# Main_Sheet.net
KiCad netlist of a schematic drawn in Altium Designer
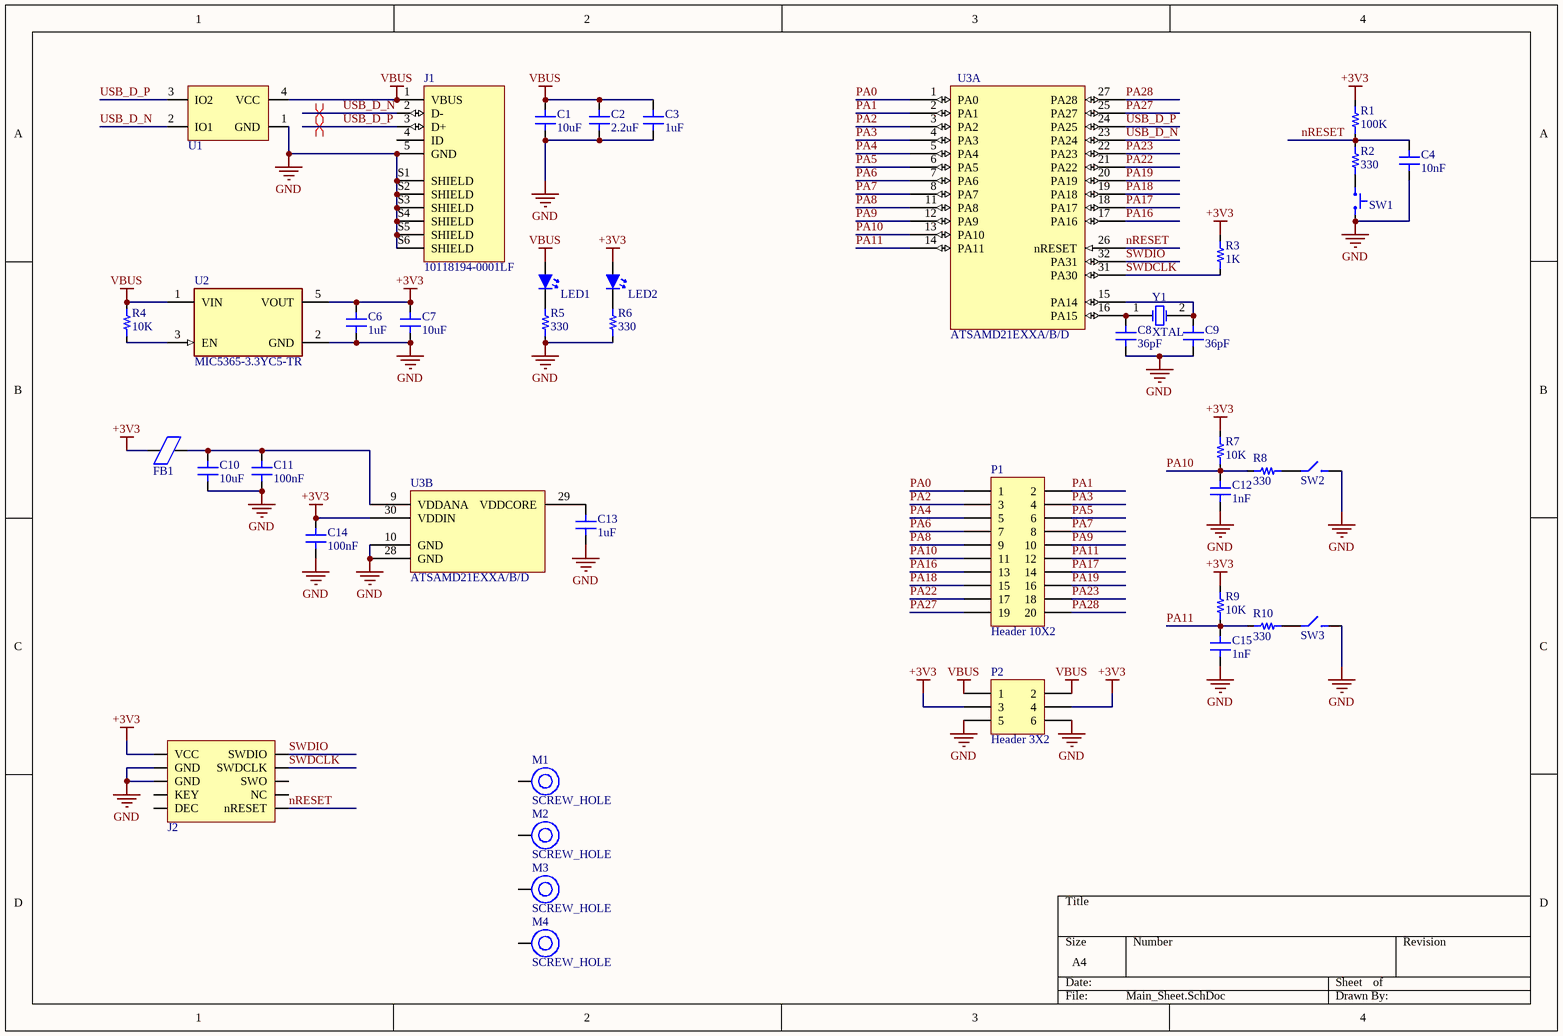
[diagram p0: Main_Sheet.SchDoc]

(export (version "E")
  (design (tool "Eeschema 10.0.6"))
  (components
    (comp (ref "C1")
      (value "10uF")
      (footprint "C0603")
      (fields (field (name "Comment") "Cap"))
      (libsource (lib "Brandon-Lib") (part "Cap"))
    )
    (comp (ref "C2")
      (value "2.2uF")
      (footprint "C0603")
      (fields (field (name "Comment") "Cap"))
      (libsource (lib "Brandon-Lib") (part "Cap"))
    )
    (comp (ref "C3")
      (value "1uF")
      (footprint "C0603")
      (fields (field (name "Comment") "Cap"))
      (libsource (lib "Brandon-Lib") (part "Cap"))
    )
    (comp (ref "C4")
      (value "10nF")
      (footprint "C0603")
      (fields (field (name "Comment") "Cap"))
      (libsource (lib "Brandon-Lib") (part "Cap"))
    )
    (comp (ref "C6")
      (value "1uF")
      (footprint "C0603")
      (fields (field (name "Comment") "Cap"))
      (libsource (lib "Brandon-Lib") (part "Cap"))
    )
    (comp (ref "C7")
      (value "10uF")
      (footprint "C0603")
      (fields (field (name "Comment") "Cap"))
      (libsource (lib "Brandon-Lib") (part "Cap"))
    )
    (comp (ref "C8")
      (value "36pF")
      (footprint "C0603")
      (fields (field (name "Comment") "Cap"))
      (libsource (lib "Brandon-Lib") (part "Cap"))
    )
    (comp (ref "C9")
      (value "36pF")
      (footprint "C0603")
      (fields (field (name "Comment") "Cap"))
      (libsource (lib "Brandon-Lib") (part "Cap"))
    )
    (comp (ref "C10")
      (value "10uF")
      (footprint "C0603")
      (fields (field (name "Comment") "Cap"))
      (libsource (lib "Brandon-Lib") (part "Cap"))
    )
    (comp (ref "C11")
      (value "100nF")
      (footprint "C0603")
      (fields (field (name "Comment") "Cap"))
      (libsource (lib "Brandon-Lib") (part "Cap"))
    )
    (comp (ref "C12")
      (value "1nF")
      (footprint "C0603")
      (fields (field (name "Comment") "Cap"))
      (libsource (lib "Brandon-Lib") (part "Cap"))
    )
    (comp (ref "C13")
      (value "1uF")
      (footprint "C0603")
      (fields (field (name "Comment") "Cap"))
      (libsource (lib "Brandon-Lib") (part "Cap"))
    )
    (comp (ref "C14")
      (value "100nF")
      (footprint "C0603")
      (fields (field (name "Comment") "Cap"))
      (libsource (lib "Brandon-Lib") (part "Cap"))
    )
    (comp (ref "C15")
      (value "1nF")
      (footprint "C0603")
      (fields (field (name "Comment") "Cap"))
      (libsource (lib "Brandon-Lib") (part "Cap"))
    )
    (comp (ref "FB1")
      (value "Ferrite Bead")
      (footprint "C0603")
      (libsource (lib "Brandon-Lib") (part "Ferrite Bead"))
    )
    (comp (ref "J1")
      (value "10118194-0001LF")
      (footprint "AMPHENOL_10103592-0001LF")
      (description "USB - micro B USB 2.0 Receptacle Connector 5 Position Surface Mount, Right Angle; Through Hole")
      (fields (field (name "MF") "Amphenol ICC"))
      (libsource (lib "Brandon-Lib") (part "10118194-0001LF"))
    )
    (comp (ref "J2")
      (value "SWD_10_PIN")
      (footprint "IPC_5X2_1.27MM")
      (libsource (lib "Brandon-Lib") (part "SWD_10_PIN"))
    )
    (comp (ref "LED1") (value "LED") (footprint "LED0805") (libsource (lib "Brandon-Lib") (part "LED")))
    (comp (ref "LED2") (value "LED") (footprint "LED0805") (libsource (lib "Brandon-Lib") (part "LED")))
    (comp (ref "M1")
      (value "SCREW_HOLE")
      (footprint "SCREW_M2")
      (libsource (lib "Brandon-Lib") (part "SCREW_HOLE"))
    )
    (comp (ref "M2")
      (value "SCREW_HOLE")
      (footprint "SCREW_M2")
      (libsource (lib "Brandon-Lib") (part "SCREW_HOLE"))
    )
    (comp (ref "M3")
      (value "SCREW_HOLE")
      (footprint "SCREW_M2")
      (libsource (lib "Brandon-Lib") (part "SCREW_HOLE"))
    )
    (comp (ref "M4")
      (value "SCREW_HOLE")
      (footprint "SCREW_M2")
      (libsource (lib "Brandon-Lib") (part "SCREW_HOLE"))
    )
    (comp (ref "P1")
      (value "Header 10X2")
      (footprint "HDR2X10")
      (description "Header, 10-Pin, Dual row")
      (fields (field (name "PUBLISHER") "Altium Limited"))
      (libsource (lib "Miscellaneous Connectors") (part "Header 10X2"))
    )
    (comp (ref "P2")
      (value "Header 3X2")
      (footprint "HDR2X3")
      (description "Header, 3-Pin, Dual row")
      (fields (field (name "PUBLISHER") "Altium Limited"))
      (libsource (lib "Miscellaneous Connectors") (part "Header 3X2"))
    )
    (comp (ref "R1")
      (value "100K")
      (footprint "R0603")
      (fields (field (name "Comment") "Res"))
      (libsource (lib "Brandon-Lib") (part "Res"))
    )
    (comp (ref "R2")
      (value "330")
      (footprint "R0603")
      (fields (field (name "Comment") "Res"))
      (libsource (lib "Brandon-Lib") (part "Res"))
    )
    (comp (ref "R3")
      (value "1K")
      (footprint "R0603")
      (fields (field (name "Comment") "Res"))
      (libsource (lib "Brandon-Lib") (part "Res"))
    )
    (comp (ref "R4")
      (value "10K")
      (footprint "R0603")
      (fields (field (name "Comment") "Res"))
      (libsource (lib "Brandon-Lib") (part "Res"))
    )
    (comp (ref "R5")
      (value "330")
      (footprint "R0603")
      (fields (field (name "Comment") "Res"))
      (libsource (lib "Brandon-Lib") (part "Res"))
    )
    (comp (ref "R6")
      (value "330")
      (footprint "R0603")
      (fields (field (name "Comment") "Res"))
      (libsource (lib "Brandon-Lib") (part "Res"))
    )
    (comp (ref "R7")
      (value "10K")
      (footprint "R0603")
      (fields (field (name "Comment") "Res"))
      (libsource (lib "Brandon-Lib") (part "Res"))
    )
    (comp (ref "R8")
      (value "330")
      (footprint "R0603")
      (fields (field (name "Comment") "Res"))
      (libsource (lib "Brandon-Lib") (part "Res"))
    )
    (comp (ref "R9")
      (value "10K")
      (footprint "R0603")
      (fields (field (name "Comment") "Res"))
      (libsource (lib "Brandon-Lib") (part "Res"))
    )
    (comp (ref "R10")
      (value "330")
      (footprint "R0603")
      (fields (field (name "Comment") "Res"))
      (libsource (lib "Brandon-Lib") (part "Res"))
    )
    (comp (ref "SW1")
      (value "Button")
      (footprint "STU-057A23AX")
      (description "Push Button")
      (libsource (lib "Brandon-Lib") (part "Button"))
    )
    (comp (ref "SW2")
      (value "CHERRY-MX")
      (footprint "CHERRY_MX_1.0")
      (libsource (lib "Brandon-Lib") (part "CHERRY-MX"))
    )
    (comp (ref "SW3")
      (value "CHERRY-MX")
      (footprint "CHERRY_MX_1.0")
      (libsource (lib "Brandon-Lib") (part "CHERRY-MX"))
    )
    (comp (ref "U1")
      (value "5.5V TVS Diode")
      (footprint "SOT143")
      (libsource (lib "Brandon-Lib") (part "PRTR5V0U2X"))
    )
    (comp (ref "U2")
      (value "MIC5365-3.3YC5-TR")
      (footprint "SOT65P210X110-5N")
      (description "Lin Reg 150mA SC-70-5")
      (libsource (lib "Brandon-Lib") (part "MIC5365-3.3YC5-TR"))
    )
    (comp (ref "U3")
      (value "ATSAMD21EXXA/B/D")
      (footprint "QFP80P900X900X120-32N")
      (libsource (lib "Brandon-Lib") (part "ATSAMD21EXXA/B/D"))
    )
    (comp (ref "Y1")
      (value "XTAL")
      (footprint "SMD-4")
      (description "ECS-120-10-33B-CKM-TR")
      (fields (field (name "PUBLISHER") "Altium Limited"))
      (libsource (lib "Miscellaneous Devices") (part "XTAL"))
    )
  )
  (nets
    (net (code "1") (name "+3V3") (class "Default")
      (node (ref "C14") (pin "1") (pinfunction "1_1") (pintype "passive"))
      (node (ref "C6") (pin "1") (pinfunction "1_1") (pintype "passive"))
      (node (ref "C7") (pin "1") (pinfunction "1_1") (pintype "passive"))
      (node (ref "FB1") (pin "1") (pinfunction "1_1") (pintype "passive"))
      (node (ref "J2") (pin "1") (pinfunction "VCC_1") (pintype "passive"))
      (node (ref "LED2") (pin "1") (pinfunction "A_1") (pintype "passive"))
      (node (ref "P2") (pin "3") (pinfunction "3_3") (pintype "passive"))
      (node (ref "P2") (pin "4") (pinfunction "4_4") (pintype "passive"))
      (node (ref "R1") (pin "1") (pinfunction "1_1") (pintype "passive"))
      (node (ref "R3") (pin "1") (pinfunction "1_1") (pintype "passive"))
      (node (ref "R7") (pin "1") (pinfunction "1_1") (pintype "passive"))
      (node (ref "R9") (pin "1") (pinfunction "1_1") (pintype "passive"))
      (node (ref "U2") (pin "5") (pinfunction "VOUT_5") (pintype "passive"))
      (node (ref "U3") (pin "30") (pinfunction "VDDIN_30") (pintype "passive"))
    )
    (net (code "2") (name "/PA0") (class "Default")
      (node (ref "P1") (pin "1") (pinfunction "1_1") (pintype "passive"))
      (node (ref "U3") (pin "1") (pinfunction "PA0_1") (pintype "bidirectional"))
    )
    (net (code "3") (name "/PA1") (class "Default")
      (node (ref "P1") (pin "2") (pinfunction "2_2") (pintype "passive"))
      (node (ref "U3") (pin "2") (pinfunction "PA1_2") (pintype "bidirectional"))
    )
    (net (code "4") (name "/PA2") (class "Default")
      (node (ref "P1") (pin "3") (pinfunction "3_3") (pintype "passive"))
      (node (ref "U3") (pin "3") (pinfunction "PA2_3") (pintype "bidirectional"))
    )
    (net (code "5") (name "/PA3") (class "Default")
      (node (ref "P1") (pin "4") (pinfunction "4_4") (pintype "passive"))
      (node (ref "U3") (pin "4") (pinfunction "PA3_4") (pintype "bidirectional"))
    )
    (net (code "6") (name "/PA4") (class "Default")
      (node (ref "P1") (pin "5") (pinfunction "5_5") (pintype "passive"))
      (node (ref "U3") (pin "5") (pinfunction "PA4_5") (pintype "bidirectional"))
    )
    (net (code "7") (name "/PA5") (class "Default")
      (node (ref "P1") (pin "6") (pinfunction "6_6") (pintype "passive"))
      (node (ref "U3") (pin "6") (pinfunction "PA5_6") (pintype "bidirectional"))
    )
    (net (code "8") (name "/PA6") (class "Default")
      (node (ref "P1") (pin "7") (pinfunction "7_7") (pintype "passive"))
      (node (ref "U3") (pin "7") (pinfunction "PA6_7") (pintype "bidirectional"))
    )
    (net (code "9") (name "/PA7") (class "Default")
      (node (ref "P1") (pin "8") (pinfunction "8_8") (pintype "passive"))
      (node (ref "U3") (pin "8") (pinfunction "PA7_8") (pintype "bidirectional"))
    )
    (net (code "10") (name "/PA8") (class "Default")
      (node (ref "P1") (pin "9") (pinfunction "9_9") (pintype "passive"))
      (node (ref "U3") (pin "11") (pinfunction "PA8_11") (pintype "bidirectional"))
    )
    (net (code "11") (name "/PA9") (class "Default")
      (node (ref "P1") (pin "10") (pinfunction "10_10") (pintype "passive"))
      (node (ref "U3") (pin "12") (pinfunction "PA9_12") (pintype "bidirectional"))
    )
    (net (code "12") (name "/PA10") (class "Default")
      (node (ref "C12") (pin "1") (pinfunction "1_1") (pintype "passive"))
      (node (ref "P1") (pin "11") (pinfunction "11_11") (pintype "passive"))
      (node (ref "R7") (pin "2") (pinfunction "2_2") (pintype "passive"))
      (node (ref "R8") (pin "1") (pinfunction "1_1") (pintype "passive"))
      (node (ref "U3") (pin "13") (pinfunction "PA10_13") (pintype "bidirectional"))
    )
    (net (code "13") (name "/PA11") (class "Default")
      (node (ref "C15") (pin "1") (pinfunction "1_1") (pintype "passive"))
      (node (ref "P1") (pin "12") (pinfunction "12_12") (pintype "passive"))
      (node (ref "R10") (pin "1") (pinfunction "1_1") (pintype "passive"))
      (node (ref "R9") (pin "2") (pinfunction "2_2") (pintype "passive"))
      (node (ref "U3") (pin "14") (pinfunction "PA11_14") (pintype "bidirectional"))
    )
    (net (code "14") (name "/PA16") (class "Default")
      (node (ref "P1") (pin "13") (pinfunction "13_13") (pintype "passive"))
      (node (ref "U3") (pin "17") (pinfunction "PA16_17") (pintype "bidirectional"))
    )
    (net (code "15") (name "/PA17") (class "Default")
      (node (ref "P1") (pin "14") (pinfunction "14_14") (pintype "passive"))
      (node (ref "U3") (pin "18") (pinfunction "PA17_18") (pintype "bidirectional"))
    )
    (net (code "16") (name "/PA18") (class "Default")
      (node (ref "P1") (pin "15") (pinfunction "15_15") (pintype "passive"))
      (node (ref "U3") (pin "19") (pinfunction "PA18_19") (pintype "bidirectional"))
    )
    (net (code "17") (name "/PA19") (class "Default")
      (node (ref "P1") (pin "16") (pinfunction "16_16") (pintype "passive"))
      (node (ref "U3") (pin "20") (pinfunction "PA19_20") (pintype "bidirectional"))
    )
    (net (code "18") (name "/PA22") (class "Default")
      (node (ref "P1") (pin "17") (pinfunction "17_17") (pintype "passive"))
      (node (ref "U3") (pin "21") (pinfunction "PA22_21") (pintype "bidirectional"))
    )
    (net (code "19") (name "/PA23") (class "Default")
      (node (ref "P1") (pin "18") (pinfunction "18_18") (pintype "passive"))
      (node (ref "U3") (pin "22") (pinfunction "PA23_22") (pintype "bidirectional"))
    )
    (net (code "20") (name "/PA27") (class "Default")
      (node (ref "P1") (pin "19") (pinfunction "19_19") (pintype "passive"))
      (node (ref "U3") (pin "25") (pinfunction "PA27_25") (pintype "bidirectional"))
    )
    (net (code "21") (name "/PA28") (class "Default")
      (node (ref "P1") (pin "20") (pinfunction "20_20") (pintype "passive"))
      (node (ref "U3") (pin "27") (pinfunction "PA28_27") (pintype "bidirectional"))
    )
    (net (code "22") (name "/SWDCLK") (class "Default")
      (node (ref "J2") (pin "4") (pinfunction "SWDCLK_4") (pintype "passive"))
      (node (ref "R3") (pin "2") (pinfunction "2_2") (pintype "passive"))
      (node (ref "U3") (pin "31") (pinfunction "PA30_31") (pintype "bidirectional"))
    )
    (net (code "23") (name "/SWDIO") (class "Default")
      (node (ref "J2") (pin "2") (pinfunction "SWDIO_2") (pintype "passive"))
      (node (ref "U3") (pin "32") (pinfunction "PA31_32") (pintype "bidirectional"))
    )
    (net (code "24") (name "/USB_D_N") (class "Default")
      (node (ref "J1") (pin "2") (pinfunction "D-_2") (pintype "bidirectional"))
      (node (ref "U1") (pin "2") (pinfunction "IO1_2") (pintype "passive"))
      (node (ref "U3") (pin "23") (pinfunction "PA24_23") (pintype "bidirectional"))
    )
    (net (code "25") (name "/USB_D_P") (class "Default")
      (node (ref "J1") (pin "3") (pinfunction "D+_3") (pintype "bidirectional"))
      (node (ref "U1") (pin "3") (pinfunction "IO2_3") (pintype "passive"))
      (node (ref "U3") (pin "24") (pinfunction "PA25_24") (pintype "bidirectional"))
    )
    (net (code "26") (name "/nRESET") (class "Default")
      (node (ref "C4") (pin "1") (pinfunction "1_1") (pintype "passive"))
      (node (ref "J2") (pin "10") (pinfunction "nRESET_10") (pintype "passive"))
      (node (ref "R1") (pin "2") (pinfunction "2_2") (pintype "passive"))
      (node (ref "R2") (pin "1") (pinfunction "1_1") (pintype "passive"))
      (node (ref "U3") (pin "26") (pinfunction "nRESET_26") (pintype "input"))
    )
    (net (code "27") (name "GND") (class "Default")
      (node (ref "C1") (pin "2") (pinfunction "2_2") (pintype "passive"))
      (node (ref "C10") (pin "2") (pinfunction "2_2") (pintype "passive"))
      (node (ref "C11") (pin "2") (pinfunction "2_2") (pintype "passive"))
      (node (ref "C12") (pin "2") (pinfunction "2_2") (pintype "passive"))
      (node (ref "C13") (pin "2") (pinfunction "2_2") (pintype "passive"))
      (node (ref "C14") (pin "2") (pinfunction "2_2") (pintype "passive"))
      (node (ref "C15") (pin "2") (pinfunction "2_2") (pintype "passive"))
      (node (ref "C2") (pin "2") (pinfunction "2_2") (pintype "passive"))
      (node (ref "C3") (pin "2") (pinfunction "2_2") (pintype "passive"))
      (node (ref "C4") (pin "2") (pinfunction "2_2") (pintype "passive"))
      (node (ref "C6") (pin "2") (pinfunction "2_2") (pintype "passive"))
      (node (ref "C7") (pin "2") (pinfunction "2_2") (pintype "passive"))
      (node (ref "C8") (pin "2") (pinfunction "2_2") (pintype "passive"))
      (node (ref "C9") (pin "2") (pinfunction "2_2") (pintype "passive"))
      (node (ref "J1") (pin "5") (pinfunction "GND_5") (pintype "passive"))
      (node (ref "J1") (pin "S1") (pinfunction "SHIELD_S1") (pintype "passive"))
      (node (ref "J1") (pin "S2") (pinfunction "SHIELD_S2") (pintype "passive"))
      (node (ref "J1") (pin "S3") (pinfunction "SHIELD_S3") (pintype "passive"))
      (node (ref "J1") (pin "S4") (pinfunction "SHIELD_S4") (pintype "passive"))
      (node (ref "J1") (pin "S5") (pinfunction "SHIELD_S5") (pintype "passive"))
      (node (ref "J1") (pin "S6") (pinfunction "SHIELD_S6") (pintype "passive"))
      (node (ref "J2") (pin "3") (pinfunction "GND_3") (pintype "passive"))
      (node (ref "J2") (pin "5") (pinfunction "GND_5") (pintype "passive"))
      (node (ref "P2") (pin "5") (pinfunction "5_5") (pintype "passive"))
      (node (ref "P2") (pin "6") (pinfunction "6_6") (pintype "passive"))
      (node (ref "R5") (pin "2") (pinfunction "2_2") (pintype "passive"))
      (node (ref "R6") (pin "2") (pinfunction "2_2") (pintype "passive"))
      (node (ref "SW1") (pin "1") (pinfunction "1_1") (pintype "passive"))
      (node (ref "SW2") (pin "2") (pinfunction "2_2") (pintype "passive"))
      (node (ref "SW3") (pin "2") (pinfunction "2_2") (pintype "passive"))
      (node (ref "U1") (pin "1") (pinfunction "GND_1") (pintype "passive"))
      (node (ref "U2") (pin "2") (pinfunction "GND_2") (pintype "power_in"))
      (node (ref "U3") (pin "10") (pinfunction "GND_10") (pintype "passive"))
      (node (ref "U3") (pin "28") (pinfunction "GND_28") (pintype "passive"))
    )
    (net (code "28") (name "Net-(LED1-K)") (class "Default")
      (node (ref "LED1") (pin "2") (pinfunction "K_2") (pintype "passive"))
      (node (ref "R5") (pin "1") (pinfunction "1_1") (pintype "passive"))
    )
    (net (code "29") (name "Net-(LED2-K)") (class "Default")
      (node (ref "LED2") (pin "2") (pinfunction "K_2") (pintype "passive"))
      (node (ref "R6") (pin "1") (pinfunction "1_1") (pintype "passive"))
    )
    (net (code "30") (name "Net-(R2-Pad2)") (class "Default")
      (node (ref "R2") (pin "2") (pinfunction "2_2") (pintype "passive"))
      (node (ref "SW1") (pin "2") (pinfunction "2_2") (pintype "passive"))
    )
    (net (code "31") (name "Net-(R8-Pad2)") (class "Default")
      (node (ref "R8") (pin "2") (pinfunction "2_2") (pintype "passive"))
      (node (ref "SW2") (pin "1") (pinfunction "1_1") (pintype "passive"))
    )
    (net (code "32") (name "Net-(R10-Pad2)") (class "Default")
      (node (ref "R10") (pin "2") (pinfunction "2_2") (pintype "passive"))
      (node (ref "SW3") (pin "1") (pinfunction "1_1") (pintype "passive"))
    )
    (net (code "33") (name "Net-(U2-EN)") (class "Default")
      (node (ref "R4") (pin "2") (pinfunction "2_2") (pintype "passive"))
      (node (ref "U2") (pin "3") (pinfunction "EN_3") (pintype "input"))
    )
    (net (code "34") (name "Net-(U3A-PA14)") (class "Default")
      (node (ref "C9") (pin "1") (pinfunction "1_1") (pintype "passive"))
      (node (ref "U3") (pin "15") (pinfunction "PA14_15") (pintype "bidirectional"))
      (node (ref "Y1") (pin "2") (pinfunction "OSC2_2") (pintype "passive"))
    )
    (net (code "35") (name "Net-(U3A-PA15)") (class "Default")
      (node (ref "C8") (pin "1") (pinfunction "1_1") (pintype "passive"))
      (node (ref "U3") (pin "16") (pinfunction "PA15_16") (pintype "bidirectional"))
      (node (ref "Y1") (pin "1") (pinfunction "OSC1_1") (pintype "passive"))
    )
    (net (code "36") (name "Net-(U3B-VDDANA)") (class "Default")
      (node (ref "C10") (pin "1") (pinfunction "1_1") (pintype "passive"))
      (node (ref "C11") (pin "1") (pinfunction "1_1") (pintype "passive"))
      (node (ref "FB1") (pin "2") (pinfunction "2_2") (pintype "passive"))
      (node (ref "U3") (pin "9") (pinfunction "VDDANA_9") (pintype "passive"))
    )
    (net (code "37") (name "Net-(U3B-VDDCORE)") (class "Default")
      (node (ref "C13") (pin "1") (pinfunction "1_1") (pintype "passive"))
      (node (ref "U3") (pin "29") (pinfunction "VDDCORE_29") (pintype "passive"))
    )
    (net (code "38") (name "VBUS") (class "Default")
      (node (ref "C1") (pin "1") (pinfunction "1_1") (pintype "passive"))
      (node (ref "C2") (pin "1") (pinfunction "1_1") (pintype "passive"))
      (node (ref "C3") (pin "1") (pinfunction "1_1") (pintype "passive"))
      (node (ref "J1") (pin "1") (pinfunction "VBUS_1") (pintype "passive"))
      (node (ref "LED1") (pin "1") (pinfunction "A_1") (pintype "passive"))
      (node (ref "P2") (pin "1") (pinfunction "1_1") (pintype "passive"))
      (node (ref "P2") (pin "2") (pinfunction "2_2") (pintype "passive"))
      (node (ref "R4") (pin "1") (pinfunction "1_1") (pintype "passive"))
      (node (ref "U1") (pin "4") (pinfunction "VCC_4") (pintype "passive"))
      (node (ref "U2") (pin "1") (pinfunction "VIN_1") (pintype "passive"))
    )
    (net (code "39") (name "unconnected-(J1-ID-Pad4)") (class "Default")
      (node (ref "J1") (pin "4") (pinfunction "ID_4") (pintype "passive"))
    )
    (net (code "40") (name "unconnected-(J2-DEC-Pad9)") (class "Default")
      (node (ref "J2") (pin "9") (pinfunction "DEC_9") (pintype "passive"))
    )
    (net (code "41") (name "unconnected-(J2-KEY-Pad7)") (class "Default")
      (node (ref "J2") (pin "7") (pinfunction "KEY_7") (pintype "passive"))
    )
    (net (code "42") (name "unconnected-(J2-NC-Pad8)") (class "Default")
      (node (ref "J2") (pin "8") (pinfunction "NC_8") (pintype "passive"))
    )
    (net (code "43") (name "unconnected-(J2-SWO-Pad6)") (class "Default")
      (node (ref "J2") (pin "6") (pinfunction "SWO_6") (pintype "passive"))
    )
    (net (code "44") (name "unconnected-(M1-Pad38)") (class "Default")
      (node (ref "M1") (pin "38") (pinfunction "38_38") (pintype "passive"))
    )
    (net (code "45") (name "unconnected-(M2-Pad38)") (class "Default")
      (node (ref "M2") (pin "38") (pinfunction "38_38") (pintype "passive"))
    )
    (net (code "46") (name "unconnected-(M3-Pad38)") (class "Default")
      (node (ref "M3") (pin "38") (pinfunction "38_38") (pintype "passive"))
    )
    (net (code "47") (name "unconnected-(M4-Pad38)") (class "Default")
      (node (ref "M4") (pin "38") (pinfunction "38_38") (pintype "passive"))
    )
  )
)
